# JFETPreamp.net
KiCad netlist of a schematic drawn in EAGLE
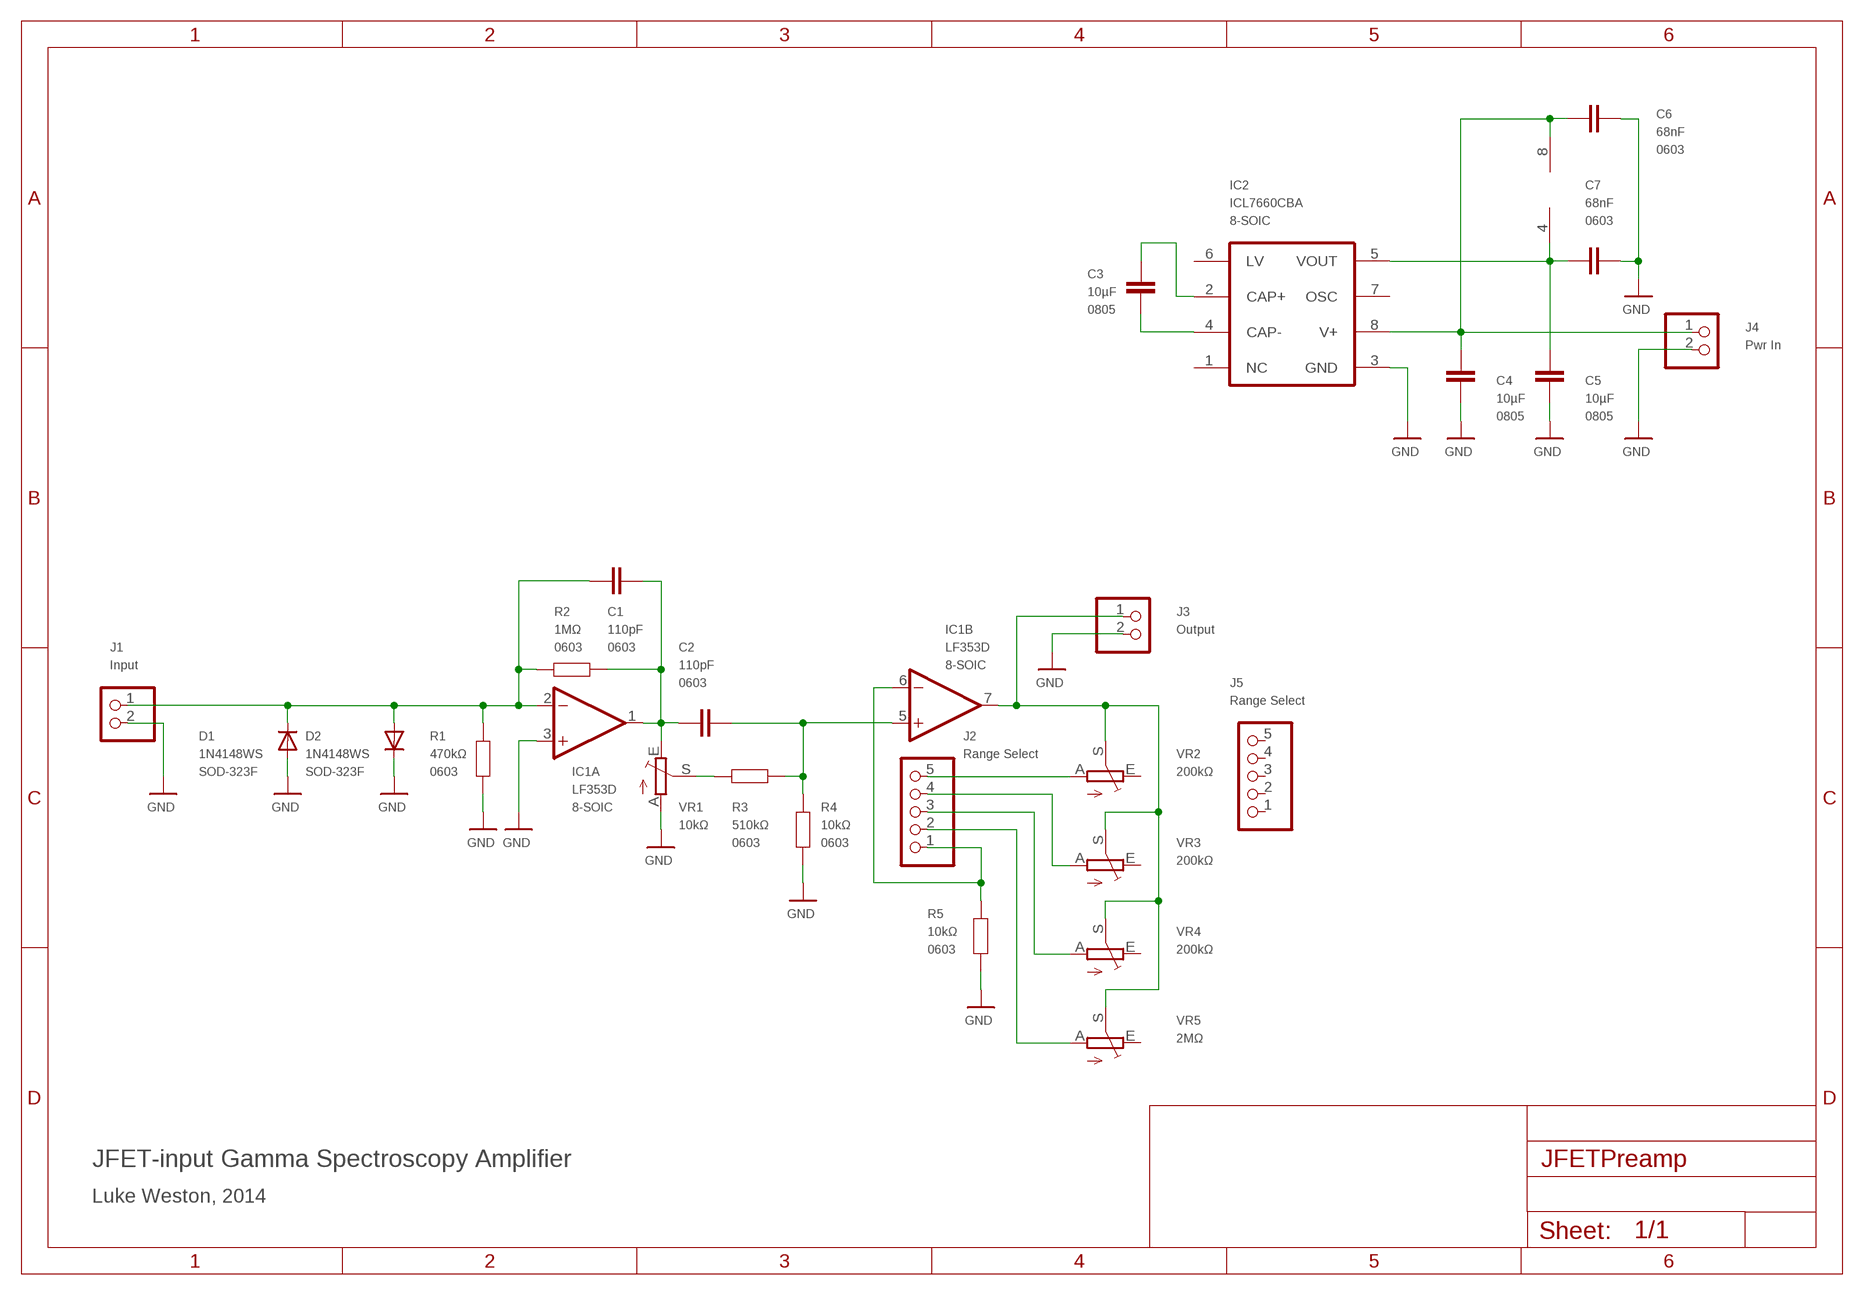
[diagram p0: schematic, sheet 1]

(export (version "E")
  (design (tool "Eeschema 10.0.6"))
  (components
    (comp (ref "C1")
      (value "110pF")
      (footprint "eagle-import:0603")
      (fields (field (name "PACKAGE") "0603"))
      (libsource (lib "eagle-import") (part "CAPACITOR0603"))
    )
    (comp (ref "C2")
      (value "110pF")
      (footprint "eagle-import:0603")
      (fields (field (name "PACKAGE") "0603"))
      (libsource (lib "eagle-import") (part "CAPACITOR0603"))
    )
    (comp (ref "C3")
      (value "10µF")
      (footprint "eagle-import:C0805K")
      (fields (field (name "PACKAGE") "0805"))
      (libsource (lib "eagle-import") (part "C-EUC0805K"))
    )
    (comp (ref "C4")
      (value "10µF")
      (footprint "eagle-import:C0805K")
      (fields (field (name "PACKAGE") "0805"))
      (libsource (lib "eagle-import") (part "C-EUC0805K"))
    )
    (comp (ref "C5")
      (value "10µF")
      (footprint "eagle-import:C0805K")
      (fields (field (name "PACKAGE") "0805"))
      (libsource (lib "eagle-import") (part "C-EUC0805K"))
    )
    (comp (ref "C6")
      (value "68nF")
      (footprint "eagle-import:0603")
      (fields (field (name "PACKAGE") "0603"))
      (libsource (lib "eagle-import") (part "CAPACITOR0603"))
    )
    (comp (ref "C7")
      (value "68nF")
      (footprint "eagle-import:0603")
      (fields (field (name "PACKAGE") "0603"))
      (libsource (lib "eagle-import") (part "CAPACITOR0603"))
    )
    (comp (ref "D1")
      (value "1N4148WS")
      (footprint "eagle-import:SOD-323")
      (fields (field (name "PACKAGE") "SOD-323F"))
      (libsource (lib "eagle-import") (part "DIODESOD"))
    )
    (comp (ref "D2")
      (value "1N4148WS")
      (footprint "eagle-import:SOD-323")
      (fields (field (name "PACKAGE") "SOD-323F"))
      (libsource (lib "eagle-import") (part "DIODESOD"))
    )
    (comp (ref "IC1")
      (value "LF353D")
      (footprint "eagle-import:SO08")
      (fields (field (name "PACKAGE") "8-SOIC"))
      (libsource (lib "eagle-import") (part "LF353D"))
    )
    (comp (ref "IC2")
      (value "ICL7660CBA")
      (footprint "eagle-import:SO08")
      (fields (field (name "MF") "MAXIM") (field (name "MPN") "ICL7660CSA") (field (name "PACKAGE") "8-SOIC"))
      (libsource (lib "eagle-import") (part "ICL7660CSA"))
    )
    (comp (ref "J1")
      (value "Input")
      (footprint "eagle-import:1X02")
      (libsource (lib "eagle-import") (part "PINHD-1X2"))
    )
    (comp (ref "J2")
      (value "Range Select")
      (footprint "eagle-import:1X05")
      (libsource (lib "eagle-import") (part "PINHD-1X5"))
    )
    (comp (ref "J3")
      (value "Output")
      (footprint "eagle-import:1X02")
      (libsource (lib "eagle-import") (part "PINHD-1X2"))
    )
    (comp (ref "J4")
      (value "Pwr In")
      (footprint "eagle-import:1X02")
      (libsource (lib "eagle-import") (part "PINHD-1X2"))
    )
    (comp (ref "J5")
      (value "Range Select")
      (footprint "eagle-import:1X05")
      (libsource (lib "eagle-import") (part "PINHD-1X5"))
    )
    (comp (ref "R1")
      (value "470kΩ")
      (footprint "eagle-import:0603")
      (fields (field (name "PACKAGE") "0603"))
      (libsource (lib "eagle-import") (part "RESISTOR-EU0603"))
    )
    (comp (ref "R2")
      (value "1MΩ")
      (footprint "eagle-import:0603")
      (fields (field (name "PACKAGE") "0603"))
      (libsource (lib "eagle-import") (part "RESISTOR-EU0603"))
    )
    (comp (ref "R3")
      (value "510kΩ")
      (footprint "eagle-import:0603")
      (fields (field (name "PACKAGE") "0603"))
      (libsource (lib "eagle-import") (part "RESISTOR-EU0603"))
    )
    (comp (ref "R4")
      (value "10kΩ")
      (footprint "eagle-import:0603")
      (fields (field (name "PACKAGE") "0603"))
      (libsource (lib "eagle-import") (part "RESISTOR-EU0603"))
    )
    (comp (ref "R5")
      (value "10kΩ")
      (footprint "eagle-import:0603")
      (fields (field (name "PACKAGE") "0603"))
      (libsource (lib "eagle-import") (part "RESISTOR-EU0603"))
    )
    (comp (ref "VR1")
      (value "10kΩ")
      (footprint "eagle-import:B25P")
      (libsource (lib "eagle-import") (part "TRIM_EU-B25P"))
    )
    (comp (ref "VR2")
      (value "200kΩ")
      (footprint "eagle-import:B25P")
      (libsource (lib "eagle-import") (part "TRIM_EU-B25P"))
    )
    (comp (ref "VR3")
      (value "200kΩ")
      (footprint "eagle-import:B25P")
      (libsource (lib "eagle-import") (part "TRIM_EU-B25P"))
    )
    (comp (ref "VR4")
      (value "200kΩ")
      (footprint "eagle-import:B25P")
      (libsource (lib "eagle-import") (part "TRIM_EU-B25P"))
    )
    (comp (ref "VR5")
      (value "2MΩ")
      (footprint "eagle-import:B25P")
      (libsource (lib "eagle-import") (part "TRIM_EU-B25P"))
    )
  )
  (nets
    (net (code "1") (name "GND") (class "Default")
      (node (ref "C4") (pin "2") (pinfunction "2_2") (pintype "passive"))
      (node (ref "C5") (pin "2") (pinfunction "2_2") (pintype "passive"))
      (node (ref "C6") (pin "1") (pinfunction "1_1") (pintype "bidirectional"))
      (node (ref "C7") (pin "1") (pinfunction "1_1") (pintype "bidirectional"))
      (node (ref "D1") (pin "2") (pinfunction "A_2") (pintype "passive"))
      (node (ref "D2") (pin "1") (pinfunction "C_1") (pintype "passive"))
      (node (ref "IC1") (pin "3") (pinfunction "+IN_3") (pintype "input"))
      (node (ref "IC2") (pin "3") (pinfunction "GND_3") (pintype "power_in"))
      (node (ref "J1") (pin "2") (pinfunction "2_2") (pintype "passive"))
      (node (ref "J3") (pin "2") (pinfunction "2_2") (pintype "passive"))
      (node (ref "J4") (pin "2") (pinfunction "2_2") (pintype "passive"))
      (node (ref "R1") (pin "1") (pinfunction "1_1") (pintype "bidirectional"))
      (node (ref "R4") (pin "2") (pinfunction "2_2") (pintype "bidirectional"))
      (node (ref "R5") (pin "2") (pinfunction "2_2") (pintype "bidirectional"))
      (node (ref "VR1") (pin "A") (pinfunction "A_A") (pintype "passive"))
    )
    (net (code "2") (name "Net-(D1-C)") (class "Default")
      (node (ref "C1") (pin "1") (pinfunction "1_1") (pintype "bidirectional"))
      (node (ref "D1") (pin "1") (pinfunction "C_1") (pintype "passive"))
      (node (ref "D2") (pin "2") (pinfunction "A_2") (pintype "passive"))
      (node (ref "IC1") (pin "2") (pinfunction "-IN_2") (pintype "input"))
      (node (ref "J1") (pin "1") (pinfunction "1_1") (pintype "passive"))
      (node (ref "R1") (pin "2") (pinfunction "2_2") (pintype "bidirectional"))
      (node (ref "R2") (pin "2") (pinfunction "2_2") (pintype "bidirectional"))
    )
    (net (code "3") (name "Net-(IC1A-OUT)") (class "Default")
      (node (ref "C1") (pin "2") (pinfunction "2_2") (pintype "bidirectional"))
      (node (ref "C2") (pin "1") (pinfunction "1_1") (pintype "bidirectional"))
      (node (ref "IC1") (pin "1") (pinfunction "OUT_1") (pintype "output"))
      (node (ref "R2") (pin "1") (pinfunction "1_1") (pintype "bidirectional"))
      (node (ref "VR1") (pin "E") (pinfunction "E_E") (pintype "passive"))
    )
    (net (code "4") (name "Net-(IC1B-+IN)") (class "Default")
      (node (ref "C2") (pin "2") (pinfunction "2_2") (pintype "bidirectional"))
      (node (ref "IC1") (pin "5") (pinfunction "+IN_5") (pintype "input"))
      (node (ref "R3") (pin "1") (pinfunction "1_1") (pintype "bidirectional"))
      (node (ref "R4") (pin "1") (pinfunction "1_1") (pintype "bidirectional"))
    )
    (net (code "5") (name "Net-(IC1B--IN)") (class "Default")
      (node (ref "IC1") (pin "6") (pinfunction "-IN_6") (pintype "input"))
      (node (ref "J2") (pin "1") (pinfunction "1_1") (pintype "passive"))
      (node (ref "R5") (pin "1") (pinfunction "1_1") (pintype "bidirectional"))
    )
    (net (code "6") (name "Net-(IC1B-OUT)") (class "Default")
      (node (ref "IC1") (pin "7") (pinfunction "OUT_7") (pintype "output"))
      (node (ref "J3") (pin "1") (pinfunction "1_1") (pintype "passive"))
      (node (ref "VR2") (pin "S") (pinfunction "S_S") (pintype "passive"))
      (node (ref "VR3") (pin "S") (pinfunction "S_S") (pintype "passive"))
      (node (ref "VR4") (pin "S") (pinfunction "S_S") (pintype "passive"))
      (node (ref "VR5") (pin "S") (pinfunction "S_S") (pintype "passive"))
    )
    (net (code "7") (name "Net-(IC1C-V+)") (class "Default")
      (node (ref "C4") (pin "1") (pinfunction "1_1") (pintype "passive"))
      (node (ref "C6") (pin "2") (pinfunction "2_2") (pintype "bidirectional"))
      (node (ref "IC1") (pin "8") (pinfunction "V+_8") (pintype "power_in"))
      (node (ref "IC2") (pin "8") (pinfunction "V+_8") (pintype "power_in"))
      (node (ref "J4") (pin "1") (pinfunction "1_1") (pintype "passive"))
    )
    (net (code "8") (name "Net-(IC1C-V-)") (class "Default")
      (node (ref "C5") (pin "1") (pinfunction "1_1") (pintype "passive"))
      (node (ref "C7") (pin "2") (pinfunction "2_2") (pintype "bidirectional"))
      (node (ref "IC1") (pin "4") (pinfunction "V-_4") (pintype "power_in"))
      (node (ref "IC2") (pin "5") (pinfunction "VOUT_5") (pintype "output"))
    )
    (net (code "9") (name "Net-(IC2-CAP+)") (class "Default")
      (node (ref "C3") (pin "1") (pinfunction "1_1") (pintype "passive"))
      (node (ref "IC2") (pin "2") (pinfunction "CAP+_2") (pintype "passive"))
    )
    (net (code "10") (name "Net-(IC2-CAP-)") (class "Default")
      (node (ref "C3") (pin "2") (pinfunction "2_2") (pintype "passive"))
      (node (ref "IC2") (pin "4") (pinfunction "CAP-_4") (pintype "passive"))
    )
    (net (code "11") (name "Net-(J2-Pad2)") (class "Default")
      (node (ref "J2") (pin "2") (pinfunction "2_2") (pintype "passive"))
      (node (ref "VR5") (pin "A") (pinfunction "A_A") (pintype "passive"))
    )
    (net (code "12") (name "Net-(J2-Pad3)") (class "Default")
      (node (ref "J2") (pin "3") (pinfunction "3_3") (pintype "passive"))
      (node (ref "VR4") (pin "A") (pinfunction "A_A") (pintype "passive"))
    )
    (net (code "13") (name "Net-(J2-Pad4)") (class "Default")
      (node (ref "J2") (pin "4") (pinfunction "4_4") (pintype "passive"))
      (node (ref "VR3") (pin "A") (pinfunction "A_A") (pintype "passive"))
    )
    (net (code "14") (name "Net-(J2-Pad5)") (class "Default")
      (node (ref "J2") (pin "5") (pinfunction "5_5") (pintype "passive"))
      (node (ref "VR2") (pin "A") (pinfunction "A_A") (pintype "passive"))
    )
    (net (code "15") (name "Net-(R3-Pad2)") (class "Default")
      (node (ref "R3") (pin "2") (pinfunction "2_2") (pintype "bidirectional"))
      (node (ref "VR1") (pin "S") (pinfunction "S_S") (pintype "passive"))
    )
    (net (code "16") (name "unconnected-(IC2-LV-Pad6)") (class "Default")
      (node (ref "IC2") (pin "6") (pinfunction "LV_6") (pintype "passive"))
    )
    (net (code "17") (name "unconnected-(IC2-NC-Pad1)") (class "Default")
      (node (ref "IC2") (pin "1") (pinfunction "NC_1") (pintype "no_connect"))
    )
    (net (code "18") (name "unconnected-(IC2-OSC-Pad7)") (class "Default")
      (node (ref "IC2") (pin "7") (pinfunction "OSC_7") (pintype "output"))
    )
    (net (code "19") (name "unconnected-(J5-Pad1)") (class "Default")
      (node (ref "J5") (pin "1") (pinfunction "1_1") (pintype "passive"))
    )
    (net (code "20") (name "unconnected-(J5-Pad2)") (class "Default")
      (node (ref "J5") (pin "2") (pinfunction "2_2") (pintype "passive"))
    )
    (net (code "21") (name "unconnected-(J5-Pad3)") (class "Default")
      (node (ref "J5") (pin "3") (pinfunction "3_3") (pintype "passive"))
    )
    (net (code "22") (name "unconnected-(J5-Pad4)") (class "Default")
      (node (ref "J5") (pin "4") (pinfunction "4_4") (pintype "passive"))
    )
    (net (code "23") (name "unconnected-(J5-Pad5)") (class "Default")
      (node (ref "J5") (pin "5") (pinfunction "5_5") (pintype "passive"))
    )
    (net (code "24") (name "unconnected-(VR2-PadE)") (class "Default")
      (node (ref "VR2") (pin "E") (pinfunction "E_E") (pintype "passive"))
    )
    (net (code "25") (name "unconnected-(VR3-PadE)") (class "Default")
      (node (ref "VR3") (pin "E") (pinfunction "E_E") (pintype "passive"))
    )
    (net (code "26") (name "unconnected-(VR4-PadE)") (class "Default")
      (node (ref "VR4") (pin "E") (pinfunction "E_E") (pintype "passive"))
    )
    (net (code "27") (name "unconnected-(VR5-PadE)") (class "Default")
      (node (ref "VR5") (pin "E") (pinfunction "E_E") (pintype "passive"))
    )
  )
)
